# AOXIM_V1_1.net
KiCad netlist of a schematic drawn in EAGLE
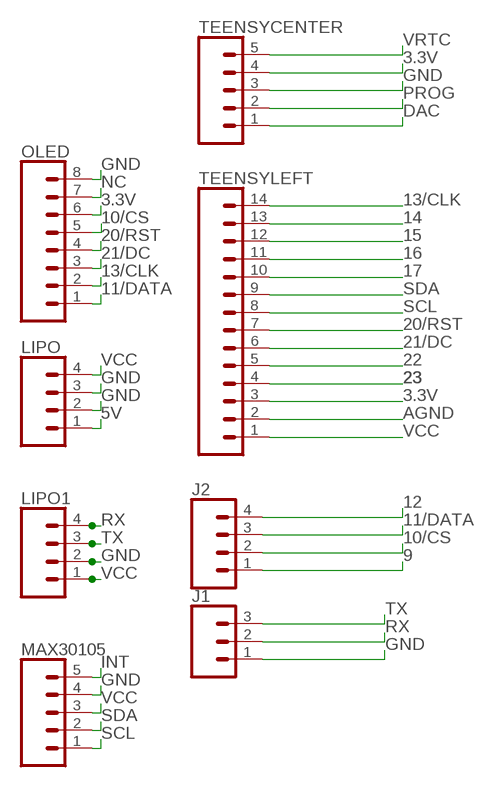
[diagram p0: schematic, sheet 1]

(export (version "E")
  (design (tool "Eeschema 10.0.6"))
  (components
    (comp (ref "J1")
      (value "CONN_03")
      (footprint "eagle-import:1X03")
      (libsource (lib "eagle-import") (part "CONN_03"))
    )
    (comp (ref "J2")
      (value "CONN_04")
      (footprint "eagle-import:1X04")
      (libsource (lib "eagle-import") (part "CONN_04"))
    )
    (comp (ref "LIPO")
      (value "CONN_04")
      (footprint "eagle-import:1X04")
      (libsource (lib "eagle-import") (part "CONN_04"))
    )
    (comp (ref "LIPO1")
      (value "CONN_04")
      (footprint "eagle-import:1X04")
      (libsource (lib "eagle-import") (part "CONN_04"))
    )
    (comp (ref "MAX30105")
      (value "CONN_05")
      (footprint "eagle-import:1X05")
      (libsource (lib "eagle-import") (part "CONN_05"))
    )
    (comp (ref "OLED")
      (value "CONN_08\"")
      (footprint "eagle-import:1X08")
      (libsource (lib "eagle-import") (part "CONN_08{dblquote}"))
    )
    (comp (ref "TEENSYCENTER")
      (value "CONN_05")
      (footprint "eagle-import:1X05")
      (libsource (lib "eagle-import") (part "CONN_05"))
    )
    (comp (ref "TEENSYLEFT")
      (value "CONN_14")
      (footprint "eagle-import:1X14")
      (libsource (lib "eagle-import") (part "CONN_14"))
    )
  )
  (nets
    (net (code "1") (name "/3.3V") (class "Default")
      (node (ref "OLED") (pin "6") (pinfunction "6_6") (pintype "passive"))
      (node (ref "TEENSYCENTER") (pin "4") (pinfunction "4_4") (pintype "passive"))
      (node (ref "TEENSYLEFT") (pin "3") (pinfunction "3_3") (pintype "passive"))
    )
    (net (code "2") (name "/5V") (class "Default")
      (node (ref "LIPO") (pin "1") (pinfunction "1_1") (pintype "passive"))
    )
    (net (code "3") (name "/9") (class "Default")
      (node (ref "J2") (pin "1") (pinfunction "1_1") (pintype "passive"))
    )
    (net (code "4") (name "/10{slash}CS") (class "Default")
      (node (ref "J2") (pin "2") (pinfunction "2_2") (pintype "passive"))
      (node (ref "OLED") (pin "5") (pinfunction "5_5") (pintype "passive"))
    )
    (net (code "5") (name "/11{slash}DATA") (class "Default")
      (node (ref "J2") (pin "3") (pinfunction "3_3") (pintype "passive"))
      (node (ref "OLED") (pin "1") (pinfunction "1_1") (pintype "passive"))
    )
    (net (code "6") (name "/12") (class "Default")
      (node (ref "J2") (pin "4") (pinfunction "4_4") (pintype "passive"))
    )
    (net (code "7") (name "/13{slash}CLK") (class "Default")
      (node (ref "OLED") (pin "2") (pinfunction "2_2") (pintype "passive"))
      (node (ref "TEENSYLEFT") (pin "14") (pinfunction "14_14") (pintype "passive"))
    )
    (net (code "8") (name "/14") (class "Default")
      (node (ref "TEENSYLEFT") (pin "13") (pinfunction "13_13") (pintype "passive"))
    )
    (net (code "9") (name "/15") (class "Default")
      (node (ref "TEENSYLEFT") (pin "12") (pinfunction "12_12") (pintype "passive"))
    )
    (net (code "10") (name "/16") (class "Default")
      (node (ref "TEENSYLEFT") (pin "11") (pinfunction "11_11") (pintype "passive"))
    )
    (net (code "11") (name "/17") (class "Default")
      (node (ref "TEENSYLEFT") (pin "10") (pinfunction "10_10") (pintype "passive"))
    )
    (net (code "12") (name "/20{slash}RST") (class "Default")
      (node (ref "OLED") (pin "4") (pinfunction "4_4") (pintype "passive"))
      (node (ref "TEENSYLEFT") (pin "7") (pinfunction "7_7") (pintype "passive"))
    )
    (net (code "13") (name "/21{slash}DC") (class "Default")
      (node (ref "OLED") (pin "3") (pinfunction "3_3") (pintype "passive"))
      (node (ref "TEENSYLEFT") (pin "6") (pinfunction "6_6") (pintype "passive"))
    )
    (net (code "14") (name "/22") (class "Default")
      (node (ref "TEENSYLEFT") (pin "5") (pinfunction "5_5") (pintype "passive"))
    )
    (net (code "15") (name "/23") (class "Default")
      (node (ref "TEENSYLEFT") (pin "4") (pinfunction "4_4") (pintype "passive"))
    )
    (net (code "16") (name "/AGND") (class "Default")
      (node (ref "TEENSYLEFT") (pin "2") (pinfunction "2_2") (pintype "passive"))
    )
    (net (code "17") (name "/DAC") (class "Default")
      (node (ref "TEENSYCENTER") (pin "1") (pinfunction "1_1") (pintype "passive"))
    )
    (net (code "18") (name "/GND") (class "Default")
      (node (ref "J1") (pin "1") (pinfunction "1_1") (pintype "passive"))
      (node (ref "LIPO") (pin "2") (pinfunction "2_2") (pintype "passive"))
      (node (ref "LIPO") (pin "3") (pinfunction "3_3") (pintype "passive"))
      (node (ref "LIPO1") (pin "2") (pinfunction "2_2") (pintype "passive"))
      (node (ref "MAX30105") (pin "4") (pinfunction "4_4") (pintype "passive"))
      (node (ref "OLED") (pin "8") (pinfunction "8_8") (pintype "passive"))
      (node (ref "TEENSYCENTER") (pin "3") (pinfunction "3_3") (pintype "passive"))
    )
    (net (code "19") (name "/INT") (class "Default")
      (node (ref "MAX30105") (pin "5") (pinfunction "5_5") (pintype "passive"))
    )
    (net (code "20") (name "/NC") (class "Default")
      (node (ref "OLED") (pin "7") (pinfunction "7_7") (pintype "passive"))
    )
    (net (code "21") (name "/PROG") (class "Default")
      (node (ref "TEENSYCENTER") (pin "2") (pinfunction "2_2") (pintype "passive"))
    )
    (net (code "22") (name "/RX") (class "Default")
      (node (ref "J1") (pin "2") (pinfunction "2_2") (pintype "passive"))
      (node (ref "LIPO1") (pin "4") (pinfunction "4_4") (pintype "passive"))
    )
    (net (code "23") (name "/SCL") (class "Default")
      (node (ref "MAX30105") (pin "1") (pinfunction "1_1") (pintype "passive"))
      (node (ref "TEENSYLEFT") (pin "8") (pinfunction "8_8") (pintype "passive"))
    )
    (net (code "24") (name "/SDA") (class "Default")
      (node (ref "MAX30105") (pin "2") (pinfunction "2_2") (pintype "passive"))
      (node (ref "TEENSYLEFT") (pin "9") (pinfunction "9_9") (pintype "passive"))
    )
    (net (code "25") (name "/TX") (class "Default")
      (node (ref "J1") (pin "3") (pinfunction "3_3") (pintype "passive"))
      (node (ref "LIPO1") (pin "3") (pinfunction "3_3") (pintype "passive"))
    )
    (net (code "26") (name "/VCC") (class "Default")
      (node (ref "LIPO") (pin "4") (pinfunction "4_4") (pintype "passive"))
      (node (ref "LIPO1") (pin "1") (pinfunction "1_1") (pintype "passive"))
      (node (ref "MAX30105") (pin "3") (pinfunction "3_3") (pintype "passive"))
      (node (ref "TEENSYLEFT") (pin "1") (pinfunction "1_1") (pintype "passive"))
    )
    (net (code "27") (name "/VRTC") (class "Default")
      (node (ref "TEENSYCENTER") (pin "5") (pinfunction "5_5") (pintype "passive"))
    )
  )
)
